# Analog_Voltmeter_Schematic.net
KiCad netlist of a schematic drawn in Altium Designer
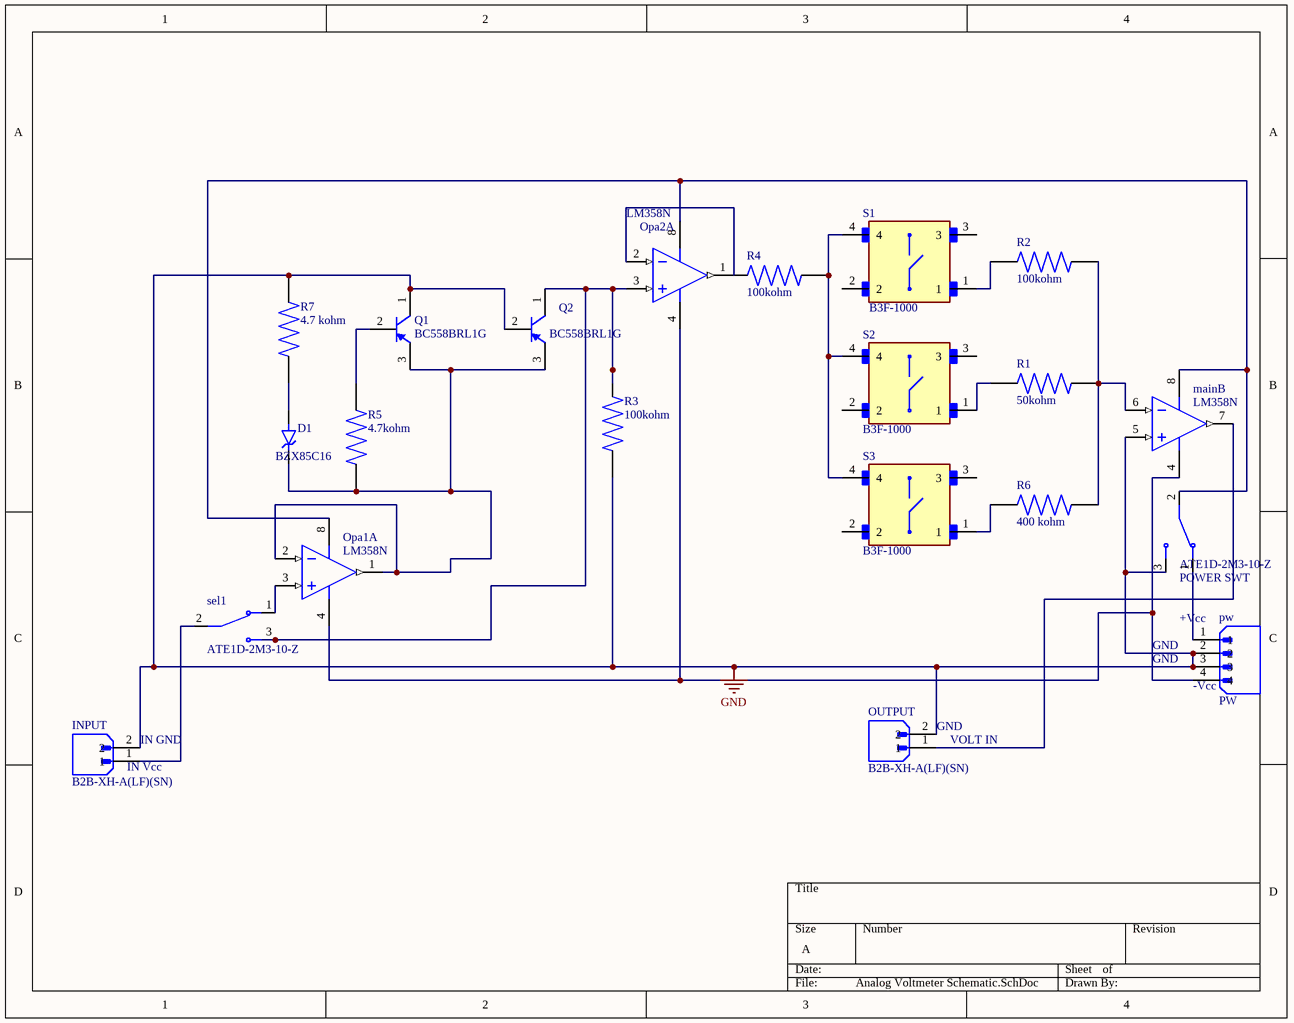
[diagram p0: Analog Voltmeter Schematic.SchDoc]

(export (version "E")
  (design (tool "Eeschema 10.0.6"))
  (components
    (comp (ref "D1")
      (value "BZX85C16")
      (footprint "DIOAD1036W73L450D282")
      (libsource (lib "BZX85C16") (part "BZX85C16"))
    )
    (comp (ref "INPUT")
      (value "B2B-XH-A(LF)(SN)")
      (footprint "JST_B2B-XH-A(LF)(SN)")
      (description "Connector Header Through Hole 2 position 0.098 (2.50mm)")
      (fields (field (name "MF") "JST Sales"))
      (libsource (lib "B2B-XH-A_LF__SN_") (part "B2B-XH-A(LF)(SN)"))
    )
    (comp (ref "main")
      (value "LM358N")
      (footprint "ONSC-PDIP-8-626-05_M")
      (description "Single Supply Dual Operational Amplifier, 3 to 32 V, 0 to 70 degC, 8-Pin PDIP, Tube")
      (fields (field (name "MANUFACTURER") "On Semiconductor"))
      (libsource (lib "Altium Content Vault") (part "ONSC-LM358_NCV2904-8"))
    )
    (comp (ref "Opa1")
      (value "LM358N")
      (footprint "ONSC-PDIP-8-626-05_M")
      (description "Single Supply Dual Operational Amplifier, 3 to 32 V, 0 to 70 degC, 8-Pin PDIP, Tube")
      (fields (field (name "MANUFACTURER") "On Semiconductor"))
      (libsource (lib "Altium Content Vault") (part "ONSC-LM358_NCV2904-8"))
    )
    (comp (ref "Opa2")
      (value "LM358N")
      (footprint "ONSC-PDIP-8-626-05_M")
      (description "Single Supply Dual Operational Amplifier, 3 to 32 V, 0 to 70 degC, 8-Pin PDIP, Tube")
      (fields (field (name "MANUFACTURER") "On Semiconductor"))
      (libsource (lib "Altium Content Vault") (part "ONSC-LM358_NCV2904-8"))
    )
    (comp (ref "OUTPUT")
      (value "B2B-XH-A(LF)(SN)")
      (footprint "JST_B2B-XH-A(LF)(SN)")
      (description "Connector Header Through Hole 2 position 0.098 (2.50mm)")
      (fields (field (name "MF") "JST Sales"))
      (libsource (lib "B2B-XH-A_LF__SN_") (part "B2B-XH-A(LF)(SN)"))
    )
    (comp (ref "POWER SWT")
      (value "ATE1D-2M3-10-Z")
      (footprint "SW_ATE1D-2M3-10-Z")
      (description "Toggle Switch SPDT Through Hole")
      (fields
        (field (name "MF") "Nidec Copal Electronics")
        (field (name "DIGI-KEY_PART_NUMBER") "563-1157-ND")
      )
      (libsource (lib "ATE1D-2M3-10-Z") (part "ATE1D-2M3-10-Z"))
    )
    (comp (ref "pw")
      (value "PW")
      (footprint "JST_B4B-XH-A(LF)(SN)")
      (description "Connector Header Through Hole 4 position 0.098 (2.50mm)")
      (fields (field (name "MP") "B4B-XH-A(LF)(SN)") (field (name "MF") "JST Sales"))
      (libsource (lib "B4B-XH-A_LF__SN_") (part "B4B-XH-A(LF)(SN)"))
    )
    (comp (ref "Q1")
      (value "BC558BRL1G")
      (footprint "ONSC-TO-92-3-29-11_AM_BL")
      (description "Amplifier Transistor, PNP Silicon, 3-Pin TO-92, Pb-Free, Tape and Reel")
      (fields (field (name "MANUFACTURER") "On Semiconductor"))
      (libsource (lib "Altium Content Vault") (part "ONSC-PNP-C1B2E3-3"))
    )
    (comp (ref "Q2")
      (value "BC558BRL1G")
      (footprint "ONSC-TO-92-3-29-11_AM_BL")
      (description "Amplifier Transistor, PNP Silicon, 3-Pin TO-92, Pb-Free, Tape and Reel")
      (fields (field (name "MANUFACTURER") "On Semiconductor"))
      (libsource (lib "Altium Content Vault") (part "ONSC-PNP-C1B2E3-3"))
    )
    (comp (ref "R1")
      (value "50kohm")
      (footprint "RESAD1081W64L635D269")
      (description "Resistor,Metal Film,ERC-55 50K .1% T-9 RNC55J5002BS B14 ¦ Vishay Dale RNC55J5002BSB14")
      (fields (field (name "MF") "Vishay") (field (name "MP") "RNC55J5002BSB14"))
      (libsource (lib "RNC55J5002BSB14") (part "RNC55J5002BSB14"))
    )
    (comp (ref "R2")
      (value "100kohm")
      (footprint "RESAD1081W64L635D269")
      (fields (field (name "MP") "RNC55H1003FSRE6") (field (name "MF") "Vishay"))
      (libsource (lib "RNC55H1003FSRE6") (part "RNC55H1003FSRE6"))
    )
    (comp (ref "R3")
      (value "100kohm")
      (footprint "RESAD1081W64L635D269")
      (fields (field (name "MP") "RNC55H1003FSRE6") (field (name "MF") "Vishay"))
      (libsource (lib "RNC55H1003FSRE6") (part "RNC55H1003FSRE6"))
    )
    (comp (ref "R4")
      (value "100kohm")
      (footprint "RESAD1081W64L635D269")
      (fields (field (name "MP") "RNC55H1003FSRE6") (field (name "MF") "Vishay"))
      (libsource (lib "RNC55H1003FSRE6") (part "RNC55H1003FSRE6"))
    )
    (comp (ref "R5")
      (value "4.7kohm")
      (footprint "RESAD1081W64L635D269")
      (description "Res Metal Film 4.7K Ohm 1% 0.125W(1/8W) Â±100ppm/Â°C 0.001% Epoxy AXL T/R")
      (fields (field (name "MF") "Vishay") (field (name "MP") "RNC55K4701FSRE6"))
      (libsource (lib "RNC55K4701FSRE6") (part "RNC55K4701FSRE6"))
    )
    (comp (ref "R6")
      (value "400 kohm")
      (footprint "RESAD1081W64L635D269")
      (description "Resistor,Metal Film,ERC-55 400K 1% T-9 RNC55J4003FS B14 ¦ Vishay Dale RNC55J4003FSB14")
      (fields (field (name "MF") "Vishay") (field (name "MP") "RNC55J4003FSB14"))
      (libsource (lib "RNC55J4003FSB14") (part "RNC55J4003FSB14"))
    )
    (comp (ref "R7")
      (value "4.7 kohm")
      (footprint "RESAD1081W64L635D269")
      (description "Res Metal Film 4.7K Ohm 1% 0.125W(1/8W) Â±100ppm/Â°C 0.001% Epoxy AXL T/R")
      (fields (field (name "MF") "Vishay") (field (name "MP") "RNC55K4701FSRE6"))
      (libsource (lib "RNC55K4701FSRE6") (part "RNC55K4701FSRE6"))
    )
    (comp (ref "S1")
      (value "B3F-1000")
      (footprint "SW_B3F-1000")
      (description "Tactile Switch SPST-NO Top Actuated Through Hole")
      (fields (field (name "MF") "Omron"))
      (libsource (lib "B3F-1000") (part "B3F-1000"))
    )
    (comp (ref "S2")
      (value "B3F-1000")
      (footprint "SW_B3F-1000")
      (description "Tactile Switch SPST-NO Top Actuated Through Hole")
      (fields (field (name "MF") "Omron"))
      (libsource (lib "B3F-1000") (part "B3F-1000"))
    )
    (comp (ref "S3")
      (value "B3F-1000")
      (footprint "SW_B3F-1000")
      (description "Tactile Switch SPST-NO Top Actuated Through Hole")
      (fields (field (name "MF") "Omron"))
      (libsource (lib "B3F-1000") (part "B3F-1000"))
    )
    (comp (ref "sel1")
      (value "ATE1D-2M3-10-Z")
      (footprint "SW_ATE1D-2M3-10-Z")
      (description "Toggle Switch SPDT Through Hole")
      (fields
        (field (name "MF") "Nidec Copal Electronics")
        (field (name "DIGI-KEY_PART_NUMBER") "563-1157-ND")
      )
      (libsource (lib "ATE1D-2M3-10-Z") (part "ATE1D-2M3-10-Z"))
    )
  )
  (nets
    (net (code "1") (name "GND") (class "Default")
      (node (ref "INPUT") (pin "2") (pinfunction "2_2") (pintype "passive"))
      (node (ref "OUTPUT") (pin "2") (pinfunction "2_2") (pintype "passive"))
      (node (ref "POWER SWT") (pin "3") (pinfunction "3_3") (pintype "passive"))
      (node (ref "Q1") (pin "1") (pinfunction "C_1") (pintype "passive"))
      (node (ref "Q2") (pin "2") (pinfunction "B_2") (pintype "passive"))
      (node (ref "R3") (pin "1") (pinfunction "1_1") (pintype "passive"))
      (node (ref "R7") (pin "2") (pinfunction "2_2") (pintype "passive"))
      (node (ref "main") (pin "5") (pinfunction "INB+_5") (pintype "input"))
      (node (ref "pw") (pin "2") (pinfunction "2_2") (pintype "passive"))
      (node (ref "pw") (pin "3") (pinfunction "3_3") (pintype "passive"))
    )
    (net (code "2") (name "Net-(D1-K)") (class "Default")
      (node (ref "D1") (pin "C") (pinfunction "K_C") (pintype "passive"))
      (node (ref "Opa1") (pin "1") (pinfunction "OUTA_1") (pintype "output"))
      (node (ref "Opa1") (pin "2") (pinfunction "INA-_2") (pintype "input"))
      (node (ref "Q1") (pin "3") (pinfunction "E_3") (pintype "passive"))
      (node (ref "Q2") (pin "3") (pinfunction "E_3") (pintype "passive"))
      (node (ref "R5") (pin "1") (pinfunction "1_1") (pintype "passive"))
    )
    (net (code "3") (name "Net-(D1-PadA)") (class "Default")
      (node (ref "D1") (pin "A") (pinfunction "A_A") (pintype "passive"))
      (node (ref "R7") (pin "1") (pinfunction "1_1") (pintype "passive"))
    )
    (net (code "4") (name "Net-(INPUT-Pad1)") (class "Default")
      (node (ref "INPUT") (pin "1") (pinfunction "1_1") (pintype "passive"))
      (node (ref "sel1") (pin "2") (pinfunction "2_2") (pintype "passive"))
    )
    (net (code "5") (name "Net-(Opa1A-INA+)") (class "Default")
      (node (ref "Opa1") (pin "3") (pinfunction "INA+_3") (pintype "input"))
      (node (ref "sel1") (pin "1") (pinfunction "1_1") (pintype "passive"))
    )
    (net (code "6") (name "Net-(Opa1A-VCC)") (class "Default")
      (node (ref "Opa1") (pin "8") (pinfunction "VCC_8") (pintype "power_in"))
      (node (ref "Opa2") (pin "8") (pinfunction "VCC_8") (pintype "power_in"))
      (node (ref "POWER SWT") (pin "2") (pinfunction "2_2") (pintype "passive"))
      (node (ref "main") (pin "8") (pinfunction "VCC_8") (pintype "power_in"))
    )
    (net (code "7") (name "Net-(Opa1A-VEE{slash}GND)") (class "Default")
      (node (ref "Opa1") (pin "4") (pinfunction "VEE/GND_4") (pintype "power_in"))
      (node (ref "Opa2") (pin "4") (pinfunction "VEE/GND_4") (pintype "power_in"))
      (node (ref "main") (pin "4") (pinfunction "VEE/GND_4") (pintype "power_in"))
      (node (ref "pw") (pin "4") (pinfunction "4_4") (pintype "passive"))
    )
    (net (code "8") (name "Net-(Opa2A-INA+)") (class "Default")
      (node (ref "Opa2") (pin "3") (pinfunction "INA+_3") (pintype "input"))
      (node (ref "Q2") (pin "1") (pinfunction "C_1") (pintype "passive"))
      (node (ref "R3") (pin "2") (pinfunction "2_2") (pintype "passive"))
      (node (ref "sel1") (pin "3") (pinfunction "3_3") (pintype "passive"))
    )
    (net (code "9") (name "Net-(Opa2A-INA-)") (class "Default")
      (node (ref "Opa2") (pin "1") (pinfunction "OUTA_1") (pintype "output"))
      (node (ref "Opa2") (pin "2") (pinfunction "INA-_2") (pintype "input"))
    )
    (net (code "10") (name "Net-(POWER SWT-Pad1)") (class "Default")
      (node (ref "POWER SWT") (pin "1") (pinfunction "1_1") (pintype "passive"))
      (node (ref "pw") (pin "1") (pinfunction "1_1") (pintype "passive"))
    )
    (net (code "11") (name "Net-(Q1-B)") (class "Default")
      (node (ref "Q1") (pin "2") (pinfunction "B_2") (pintype "passive"))
      (node (ref "R5") (pin "2") (pinfunction "2_2") (pintype "passive"))
    )
    (net (code "12") (name "Net-(R1-Pad2)") (class "Default")
      (node (ref "R1") (pin "2") (pinfunction "2_2") (pintype "passive"))
      (node (ref "S2") (pin "1") (pinfunction "1_1") (pintype "passive"))
    )
    (net (code "13") (name "Net-(R2-Pad1)") (class "Default")
      (node (ref "R2") (pin "1") (pinfunction "1_1") (pintype "passive"))
      (node (ref "S1") (pin "1") (pinfunction "1_1") (pintype "passive"))
    )
    (net (code "14") (name "Net-(R4-Pad2)") (class "Default")
      (node (ref "R4") (pin "2") (pinfunction "2_2") (pintype "passive"))
      (node (ref "S1") (pin "4") (pinfunction "4_4") (pintype "passive"))
      (node (ref "S2") (pin "4") (pinfunction "4_4") (pintype "passive"))
      (node (ref "S3") (pin "4") (pinfunction "4_4") (pintype "passive"))
    )
    (net (code "15") (name "Net-(R6-Pad1)") (class "Default")
      (node (ref "R6") (pin "1") (pinfunction "1_1") (pintype "passive"))
      (node (ref "S3") (pin "1") (pinfunction "1_1") (pintype "passive"))
    )
    (net (code "16") (name "Net-(mainB-INB-)") (class "Default")
      (node (ref "R1") (pin "1") (pinfunction "1_1") (pintype "passive"))
      (node (ref "R2") (pin "2") (pinfunction "2_2") (pintype "passive"))
      (node (ref "R6") (pin "2") (pinfunction "2_2") (pintype "passive"))
      (node (ref "main") (pin "6") (pinfunction "INB-_6") (pintype "input"))
    )
    (net (code "17") (name "Net-(mainB-OUTB)") (class "Default")
      (node (ref "OUTPUT") (pin "1") (pinfunction "1_1") (pintype "passive"))
      (node (ref "main") (pin "7") (pinfunction "OUTB_7") (pintype "output"))
    )
    (net (code "18") (name "unconnected-(R4-Pad1)") (class "Default")
      (node (ref "R4") (pin "1") (pinfunction "1_1") (pintype "passive"))
    )
    (net (code "19") (name "unconnected-(S1-Pad2)") (class "Default")
      (node (ref "S1") (pin "2") (pinfunction "2_2") (pintype "passive"))
    )
    (net (code "20") (name "unconnected-(S1-Pad3)") (class "Default")
      (node (ref "S1") (pin "3") (pinfunction "3_3") (pintype "passive"))
    )
    (net (code "21") (name "unconnected-(S2-Pad2)") (class "Default")
      (node (ref "S2") (pin "2") (pinfunction "2_2") (pintype "passive"))
    )
    (net (code "22") (name "unconnected-(S2-Pad3)") (class "Default")
      (node (ref "S2") (pin "3") (pinfunction "3_3") (pintype "passive"))
    )
    (net (code "23") (name "unconnected-(S3-Pad2)") (class "Default")
      (node (ref "S3") (pin "2") (pinfunction "2_2") (pintype "passive"))
    )
    (net (code "24") (name "unconnected-(S3-Pad3)") (class "Default")
      (node (ref "S3") (pin "3") (pinfunction "3_3") (pintype "passive"))
    )
  )
)
